# Layer2_v1_0.net
KiCad netlist of a schematic drawn in EAGLE
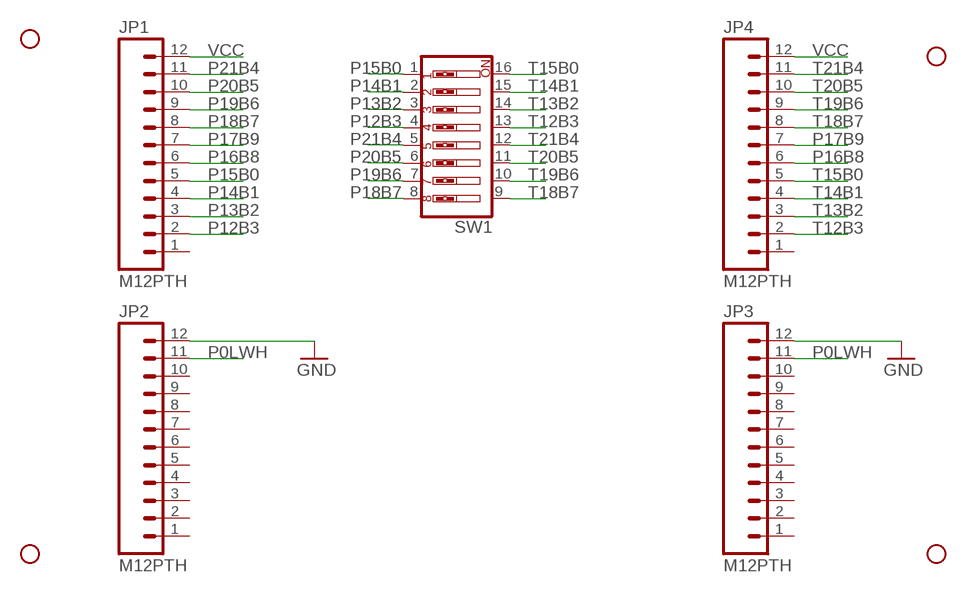
[diagram p0: schematic, sheet 1]

(export (version "E")
  (design (tool "Eeschema 10.0.6"))
  (components
    (comp (ref "JP1")
      (value "M12PTH")
      (footprint "eagle-import:1X12")
      (libsource (lib "eagle-import") (part "M12PTH"))
    )
    (comp (ref "JP2")
      (value "M12PTH")
      (footprint "eagle-import:1X12")
      (libsource (lib "eagle-import") (part "M12PTH"))
    )
    (comp (ref "JP3")
      (value "M12PTH")
      (footprint "eagle-import:1X12")
      (libsource (lib "eagle-import") (part "M12PTH"))
    )
    (comp (ref "JP4")
      (value "M12PTH")
      (footprint "eagle-import:1X12")
      (libsource (lib "eagle-import") (part "M12PTH"))
    )
    (comp (ref "JP5")
      (value "STAND-OFF")
      (footprint "eagle-import:STAND-OFF")
      (libsource (lib "eagle-import") (part "STAND-OFF"))
    )
    (comp (ref "JP6")
      (value "STAND-OFF")
      (footprint "eagle-import:STAND-OFF")
      (libsource (lib "eagle-import") (part "STAND-OFF"))
    )
    (comp (ref "JP7")
      (value "STAND-OFF")
      (footprint "eagle-import:STAND-OFF")
      (libsource (lib "eagle-import") (part "STAND-OFF"))
    )
    (comp (ref "JP8")
      (value "STAND-OFF")
      (footprint "eagle-import:STAND-OFF")
      (libsource (lib "eagle-import") (part "STAND-OFF"))
    )
    (comp (ref "SW1")
      (value "SW_DIP-8")
      (footprint "eagle-import:DIPSWITCH-08")
      (libsource (lib "eagle-import") (part "SW_DIP-8"))
    )
  )
  (nets
    (net (code "1") (name "/P0LWH") (class "Default")
      (node (ref "JP2") (pin "11") (pinfunction "11_11") (pintype "passive"))
      (node (ref "JP3") (pin "11") (pinfunction "11_11") (pintype "passive"))
    )
    (net (code "2") (name "/P12B3") (class "Default")
      (node (ref "JP1") (pin "2") (pinfunction "2_2") (pintype "passive"))
      (node (ref "SW1") (pin "4") (pinfunction "4_4") (pintype "passive"))
    )
    (net (code "3") (name "/P13B2") (class "Default")
      (node (ref "JP1") (pin "3") (pinfunction "3_3") (pintype "passive"))
      (node (ref "SW1") (pin "3") (pinfunction "3_3") (pintype "passive"))
    )
    (net (code "4") (name "/P14B1") (class "Default")
      (node (ref "JP1") (pin "4") (pinfunction "4_4") (pintype "passive"))
      (node (ref "SW1") (pin "2") (pinfunction "2_2") (pintype "passive"))
    )
    (net (code "5") (name "/P15B0") (class "Default")
      (node (ref "JP1") (pin "5") (pinfunction "5_5") (pintype "passive"))
      (node (ref "SW1") (pin "1") (pinfunction "1_1") (pintype "passive"))
    )
    (net (code "6") (name "/P16B8") (class "Default")
      (node (ref "JP1") (pin "6") (pinfunction "6_6") (pintype "passive"))
      (node (ref "JP4") (pin "6") (pinfunction "6_6") (pintype "passive"))
    )
    (net (code "7") (name "/P17B9") (class "Default")
      (node (ref "JP1") (pin "7") (pinfunction "7_7") (pintype "passive"))
      (node (ref "JP4") (pin "7") (pinfunction "7_7") (pintype "passive"))
    )
    (net (code "8") (name "/P18B7") (class "Default")
      (node (ref "JP1") (pin "8") (pinfunction "8_8") (pintype "passive"))
      (node (ref "SW1") (pin "8") (pinfunction "8_8") (pintype "passive"))
    )
    (net (code "9") (name "/P19B6") (class "Default")
      (node (ref "JP1") (pin "9") (pinfunction "9_9") (pintype "passive"))
      (node (ref "SW1") (pin "7") (pinfunction "7_7") (pintype "passive"))
    )
    (net (code "10") (name "/P20B5") (class "Default")
      (node (ref "JP1") (pin "10") (pinfunction "10_10") (pintype "passive"))
      (node (ref "SW1") (pin "6") (pinfunction "6_6") (pintype "passive"))
    )
    (net (code "11") (name "/P21B4") (class "Default")
      (node (ref "JP1") (pin "11") (pinfunction "11_11") (pintype "passive"))
      (node (ref "SW1") (pin "5") (pinfunction "5_5") (pintype "passive"))
    )
    (net (code "12") (name "/T12B3") (class "Default")
      (node (ref "JP4") (pin "2") (pinfunction "2_2") (pintype "passive"))
      (node (ref "SW1") (pin "13") (pinfunction "13_13") (pintype "passive"))
    )
    (net (code "13") (name "/T13B2") (class "Default")
      (node (ref "JP4") (pin "3") (pinfunction "3_3") (pintype "passive"))
      (node (ref "SW1") (pin "14") (pinfunction "14_14") (pintype "passive"))
    )
    (net (code "14") (name "/T14B1") (class "Default")
      (node (ref "JP4") (pin "4") (pinfunction "4_4") (pintype "passive"))
      (node (ref "SW1") (pin "15") (pinfunction "15_15") (pintype "passive"))
    )
    (net (code "15") (name "/T15B0") (class "Default")
      (node (ref "JP4") (pin "5") (pinfunction "5_5") (pintype "passive"))
      (node (ref "SW1") (pin "16") (pinfunction "16_16") (pintype "passive"))
    )
    (net (code "16") (name "/T18B7") (class "Default")
      (node (ref "JP4") (pin "8") (pinfunction "8_8") (pintype "passive"))
      (node (ref "SW1") (pin "9") (pinfunction "9_9") (pintype "passive"))
    )
    (net (code "17") (name "/T19B6") (class "Default")
      (node (ref "JP4") (pin "9") (pinfunction "9_9") (pintype "passive"))
      (node (ref "SW1") (pin "10") (pinfunction "10_10") (pintype "passive"))
    )
    (net (code "18") (name "/T20B5") (class "Default")
      (node (ref "JP4") (pin "10") (pinfunction "10_10") (pintype "passive"))
      (node (ref "SW1") (pin "11") (pinfunction "11_11") (pintype "passive"))
    )
    (net (code "19") (name "/T21B4") (class "Default")
      (node (ref "JP4") (pin "11") (pinfunction "11_11") (pintype "passive"))
      (node (ref "SW1") (pin "12") (pinfunction "12_12") (pintype "passive"))
    )
    (net (code "20") (name "/VCC") (class "Default")
      (node (ref "JP1") (pin "12") (pinfunction "12_12") (pintype "passive"))
      (node (ref "JP4") (pin "12") (pinfunction "12_12") (pintype "passive"))
    )
    (net (code "21") (name "GND") (class "Default")
      (node (ref "JP2") (pin "12") (pinfunction "12_12") (pintype "passive"))
      (node (ref "JP3") (pin "12") (pinfunction "12_12") (pintype "passive"))
    )
    (net (code "22") (name "unconnected-(JP1-Pad1)") (class "Default")
      (node (ref "JP1") (pin "1") (pinfunction "1_1") (pintype "passive"))
    )
    (net (code "23") (name "unconnected-(JP2-Pad1)") (class "Default")
      (node (ref "JP2") (pin "1") (pinfunction "1_1") (pintype "passive"))
    )
    (net (code "24") (name "unconnected-(JP2-Pad2)") (class "Default")
      (node (ref "JP2") (pin "2") (pinfunction "2_2") (pintype "passive"))
    )
    (net (code "25") (name "unconnected-(JP2-Pad3)") (class "Default")
      (node (ref "JP2") (pin "3") (pinfunction "3_3") (pintype "passive"))
    )
    (net (code "26") (name "unconnected-(JP2-Pad4)") (class "Default")
      (node (ref "JP2") (pin "4") (pinfunction "4_4") (pintype "passive"))
    )
    (net (code "27") (name "unconnected-(JP2-Pad5)") (class "Default")
      (node (ref "JP2") (pin "5") (pinfunction "5_5") (pintype "passive"))
    )
    (net (code "28") (name "unconnected-(JP2-Pad6)") (class "Default")
      (node (ref "JP2") (pin "6") (pinfunction "6_6") (pintype "passive"))
    )
    (net (code "29") (name "unconnected-(JP2-Pad7)") (class "Default")
      (node (ref "JP2") (pin "7") (pinfunction "7_7") (pintype "passive"))
    )
    (net (code "30") (name "unconnected-(JP2-Pad8)") (class "Default")
      (node (ref "JP2") (pin "8") (pinfunction "8_8") (pintype "passive"))
    )
    (net (code "31") (name "unconnected-(JP2-Pad9)") (class "Default")
      (node (ref "JP2") (pin "9") (pinfunction "9_9") (pintype "passive"))
    )
    (net (code "32") (name "unconnected-(JP2-Pad10)") (class "Default")
      (node (ref "JP2") (pin "10") (pinfunction "10_10") (pintype "passive"))
    )
    (net (code "33") (name "unconnected-(JP3-Pad1)") (class "Default")
      (node (ref "JP3") (pin "1") (pinfunction "1_1") (pintype "passive"))
    )
    (net (code "34") (name "unconnected-(JP3-Pad2)") (class "Default")
      (node (ref "JP3") (pin "2") (pinfunction "2_2") (pintype "passive"))
    )
    (net (code "35") (name "unconnected-(JP3-Pad3)") (class "Default")
      (node (ref "JP3") (pin "3") (pinfunction "3_3") (pintype "passive"))
    )
    (net (code "36") (name "unconnected-(JP3-Pad4)") (class "Default")
      (node (ref "JP3") (pin "4") (pinfunction "4_4") (pintype "passive"))
    )
    (net (code "37") (name "unconnected-(JP3-Pad5)") (class "Default")
      (node (ref "JP3") (pin "5") (pinfunction "5_5") (pintype "passive"))
    )
    (net (code "38") (name "unconnected-(JP3-Pad6)") (class "Default")
      (node (ref "JP3") (pin "6") (pinfunction "6_6") (pintype "passive"))
    )
    (net (code "39") (name "unconnected-(JP3-Pad7)") (class "Default")
      (node (ref "JP3") (pin "7") (pinfunction "7_7") (pintype "passive"))
    )
    (net (code "40") (name "unconnected-(JP3-Pad8)") (class "Default")
      (node (ref "JP3") (pin "8") (pinfunction "8_8") (pintype "passive"))
    )
    (net (code "41") (name "unconnected-(JP3-Pad9)") (class "Default")
      (node (ref "JP3") (pin "9") (pinfunction "9_9") (pintype "passive"))
    )
    (net (code "42") (name "unconnected-(JP3-Pad10)") (class "Default")
      (node (ref "JP3") (pin "10") (pinfunction "10_10") (pintype "passive"))
    )
    (net (code "43") (name "unconnected-(JP4-Pad1)") (class "Default")
      (node (ref "JP4") (pin "1") (pinfunction "1_1") (pintype "passive"))
    )
  )
)
